# sensor.net
KiCad netlist of a schematic drawn in EAGLE
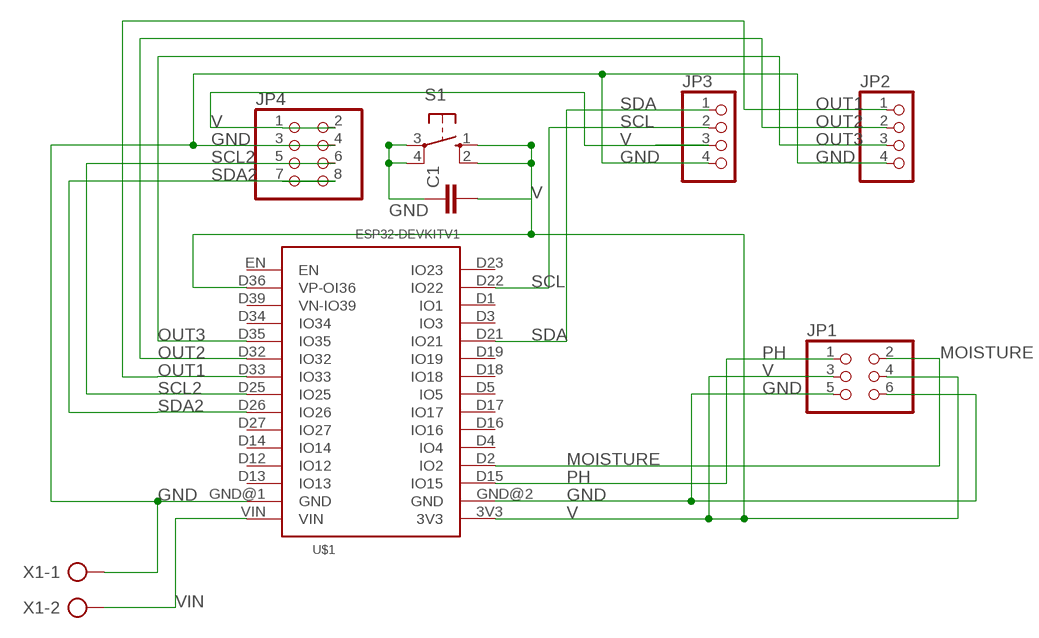
[diagram p0: schematic, sheet 1]

(export (version "E")
  (design (tool "Eeschema 10.0.6"))
  (components
    (comp (ref "C1")
      (value "C-EU050-030X075")
      (footprint "eagle-import:C050-030X075")
      (libsource (lib "eagle-import") (part "C-EU050-030X075"))
    )
    (comp (ref "JP1")
      (value "PINHD-2X3")
      (footprint "eagle-import:2X03")
      (libsource (lib "eagle-import") (part "PINHD-2X3"))
    )
    (comp (ref "JP2")
      (value "PINHD-1X4")
      (footprint "eagle-import:1X04")
      (libsource (lib "eagle-import") (part "PINHD-1X4"))
    )
    (comp (ref "JP3")
      (value "PINHD-1X4")
      (footprint "eagle-import:1X04")
      (libsource (lib "eagle-import") (part "PINHD-1X4"))
    )
    (comp (ref "JP4")
      (value "PINHD-2X4")
      (footprint "eagle-import:2X04")
      (libsource (lib "eagle-import") (part "PINHD-2X4"))
    )
    (comp (ref "S1")
      (value "10-XX")
      (footprint "eagle-import:B3F-10XX")
      (fields (field (name "MPN") "B3F-1000"))
      (libsource (lib "eagle-import") (part "10-XX"))
    )
    (comp (ref "U$1")
      (value "ESP32DEVKITV1")
      (footprint "eagle-import:ESP32-DEVKITV1")
      (libsource (lib "eagle-import") (part "ESP32DEVKITV1"))
    )
    (comp (ref "X1")
      (value "AK300/2")
      (footprint "eagle-import:AK300_2")
      (libsource (lib "eagle-import") (part "AK300/2"))
    )
  )
  (nets
    (net (code "1") (name "/GND") (class "Default")
      (node (ref "C1") (pin "1") (pinfunction "1_1") (pintype "passive"))
      (node (ref "JP1") (pin "5") (pinfunction "5_5") (pintype "passive"))
      (node (ref "JP1") (pin "6") (pinfunction "6_6") (pintype "passive"))
      (node (ref "JP2") (pin "4") (pinfunction "4_4") (pintype "passive"))
      (node (ref "JP3") (pin "4") (pinfunction "4_4") (pintype "passive"))
      (node (ref "JP4") (pin "3") (pinfunction "3_3") (pintype "passive"))
      (node (ref "JP4") (pin "4") (pinfunction "4_4") (pintype "passive"))
      (node (ref "S1") (pin "3") (pinfunction "P_3") (pintype "passive"))
      (node (ref "S1") (pin "4") (pinfunction "P1_4") (pintype "passive"))
      (node (ref "U$1") (pin "GND@1") (pinfunction "GND_GND@1") (pintype "bidirectional"))
      (node (ref "U$1") (pin "GND@2") (pinfunction "GND_GND@2") (pintype "bidirectional"))
      (node (ref "X1") (pin "1") (pinfunction "KL_1") (pintype "passive"))
    )
    (net (code "2") (name "/MOISTURE") (class "Default")
      (node (ref "JP1") (pin "2") (pinfunction "2_2") (pintype "passive"))
      (node (ref "U$1") (pin "D2") (pinfunction "IO2_D2") (pintype "bidirectional"))
    )
    (net (code "3") (name "/OUT1") (class "Default")
      (node (ref "JP2") (pin "1") (pinfunction "1_1") (pintype "passive"))
      (node (ref "U$1") (pin "D33") (pinfunction "IO33_D33") (pintype "bidirectional"))
    )
    (net (code "4") (name "/OUT2") (class "Default")
      (node (ref "JP2") (pin "2") (pinfunction "2_2") (pintype "passive"))
      (node (ref "U$1") (pin "D32") (pinfunction "IO32_D32") (pintype "bidirectional"))
    )
    (net (code "5") (name "/OUT3") (class "Default")
      (node (ref "JP2") (pin "3") (pinfunction "3_3") (pintype "passive"))
      (node (ref "U$1") (pin "D35") (pinfunction "IO35_D35") (pintype "bidirectional"))
    )
    (net (code "6") (name "/PH") (class "Default")
      (node (ref "JP1") (pin "1") (pinfunction "1_1") (pintype "passive"))
      (node (ref "U$1") (pin "D15") (pinfunction "IO15_D15") (pintype "bidirectional"))
    )
    (net (code "7") (name "/SCL") (class "Default")
      (node (ref "JP3") (pin "2") (pinfunction "2_2") (pintype "passive"))
      (node (ref "U$1") (pin "D22") (pinfunction "IO22_D22") (pintype "bidirectional"))
    )
    (net (code "8") (name "/SCL2") (class "Default")
      (node (ref "JP4") (pin "5") (pinfunction "5_5") (pintype "passive"))
      (node (ref "JP4") (pin "6") (pinfunction "6_6") (pintype "passive"))
      (node (ref "U$1") (pin "D25") (pinfunction "IO25_D25") (pintype "bidirectional"))
    )
    (net (code "9") (name "/SDA") (class "Default")
      (node (ref "JP3") (pin "1") (pinfunction "1_1") (pintype "passive"))
      (node (ref "U$1") (pin "D21") (pinfunction "IO21_D21") (pintype "bidirectional"))
    )
    (net (code "10") (name "/SDA2") (class "Default")
      (node (ref "JP4") (pin "7") (pinfunction "7_7") (pintype "passive"))
      (node (ref "JP4") (pin "8") (pinfunction "8_8") (pintype "passive"))
      (node (ref "U$1") (pin "D26") (pinfunction "IO26_D26") (pintype "bidirectional"))
    )
    (net (code "11") (name "/V") (class "Default")
      (node (ref "C1") (pin "2") (pinfunction "2_2") (pintype "passive"))
      (node (ref "JP1") (pin "3") (pinfunction "3_3") (pintype "passive"))
      (node (ref "JP1") (pin "4") (pinfunction "4_4") (pintype "passive"))
      (node (ref "JP3") (pin "3") (pinfunction "3_3") (pintype "passive"))
      (node (ref "JP4") (pin "1") (pinfunction "1_1") (pintype "passive"))
      (node (ref "JP4") (pin "2") (pinfunction "2_2") (pintype "passive"))
      (node (ref "S1") (pin "1") (pinfunction "S_1") (pintype "passive"))
      (node (ref "S1") (pin "2") (pinfunction "S1_2") (pintype "passive"))
      (node (ref "U$1") (pin "3V3") (pinfunction "3V3_3V3") (pintype "bidirectional"))
      (node (ref "U$1") (pin "D36") (pinfunction "VP-OI36_D36") (pintype "bidirectional"))
    )
    (net (code "12") (name "/VIN") (class "Default")
      (node (ref "U$1") (pin "VIN") (pinfunction "VIN_VIN") (pintype "bidirectional"))
      (node (ref "X1") (pin "2") (pinfunction "KL_2") (pintype "passive"))
    )
    (net (code "13") (name "unconnected-(U$1-IO1-PadD1)") (class "Default")
      (node (ref "U$1") (pin "D1") (pinfunction "IO1_D1") (pintype "bidirectional"))
    )
    (net (code "14") (name "unconnected-(U$1-IO3-PadD3)") (class "Default")
      (node (ref "U$1") (pin "D3") (pinfunction "IO3_D3") (pintype "bidirectional"))
    )
    (net (code "15") (name "unconnected-(U$1-IO4-PadD4)") (class "Default")
      (node (ref "U$1") (pin "D4") (pinfunction "IO4_D4") (pintype "bidirectional"))
    )
    (net (code "16") (name "unconnected-(U$1-IO5-PadD5)") (class "Default")
      (node (ref "U$1") (pin "D5") (pinfunction "IO5_D5") (pintype "bidirectional"))
    )
    (net (code "17") (name "unconnected-(U$1-IO12-PadD12)") (class "Default")
      (node (ref "U$1") (pin "D12") (pinfunction "IO12_D12") (pintype "bidirectional"))
    )
    (net (code "18") (name "unconnected-(U$1-IO13-PadD13)") (class "Default")
      (node (ref "U$1") (pin "D13") (pinfunction "IO13_D13") (pintype "bidirectional"))
    )
    (net (code "19") (name "unconnected-(U$1-IO14-PadD14)") (class "Default")
      (node (ref "U$1") (pin "D14") (pinfunction "IO14_D14") (pintype "bidirectional"))
    )
    (net (code "20") (name "unconnected-(U$1-IO16-PadD16)") (class "Default")
      (node (ref "U$1") (pin "D16") (pinfunction "IO16_D16") (pintype "bidirectional"))
    )
    (net (code "21") (name "unconnected-(U$1-IO17-PadD17)") (class "Default")
      (node (ref "U$1") (pin "D17") (pinfunction "IO17_D17") (pintype "bidirectional"))
    )
    (net (code "22") (name "unconnected-(U$1-IO18-PadD18)") (class "Default")
      (node (ref "U$1") (pin "D18") (pinfunction "IO18_D18") (pintype "bidirectional"))
    )
    (net (code "23") (name "unconnected-(U$1-IO19-PadD19)") (class "Default")
      (node (ref "U$1") (pin "D19") (pinfunction "IO19_D19") (pintype "bidirectional"))
    )
    (net (code "24") (name "unconnected-(U$1-IO23-PadD23)") (class "Default")
      (node (ref "U$1") (pin "D23") (pinfunction "IO23_D23") (pintype "bidirectional"))
    )
    (net (code "25") (name "unconnected-(U$1-IO27-PadD27)") (class "Default")
      (node (ref "U$1") (pin "D27") (pinfunction "IO27_D27") (pintype "bidirectional"))
    )
    (net (code "26") (name "unconnected-(U$1-IO34-PadD34)") (class "Default")
      (node (ref "U$1") (pin "D34") (pinfunction "IO34_D34") (pintype "bidirectional"))
    )
    (net (code "27") (name "unconnected-(U$1-PadEN)") (class "Default")
      (node (ref "U$1") (pin "EN") (pinfunction "EN_EN") (pintype "bidirectional"))
    )
    (net (code "28") (name "unconnected-(U$1-VN-IO39-PadD39)") (class "Default")
      (node (ref "U$1") (pin "D39") (pinfunction "VN-IO39_D39") (pintype "bidirectional"))
    )
  )
)
